# 4_shkb_lite_mini_bt_power.net
KiCad netlist of a schematic drawn in Altium Designer
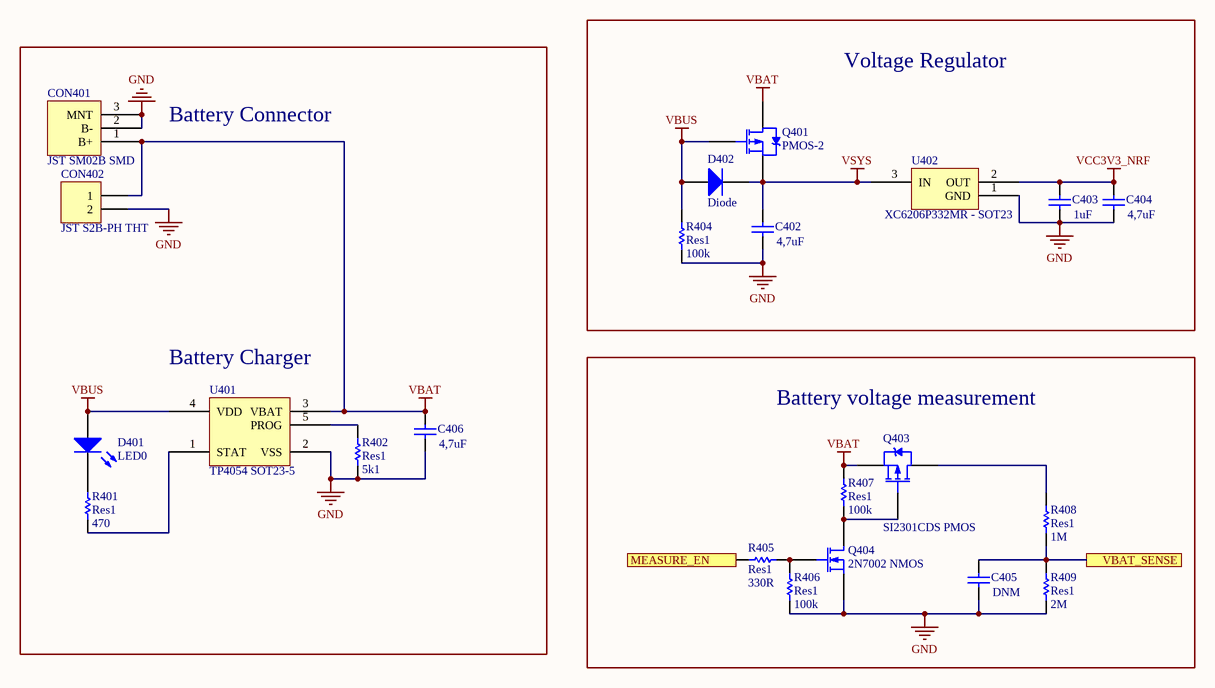
[diagram p0: 4_shkb_lite_mini_bt_power.SchDoc]

(export (version "E")
  (design (tool "Eeschema 10.0.6"))
  (components
    (comp (ref "C402")
      (value "4,7uF")
      (footprint "C0603[1608]")
      (description "Capacitor")
      (fields (field (name "LCSC PART #") "C19666") (field (name "MRF.PART") "CL10A475KO8NNNC"))
      (libsource (lib "Miscellaneous Devices") (part "Cap"))
    )
    (comp (ref "C403")
      (value "1uF")
      (footprint "C0603[1608]")
      (description "Capacitor")
      (fields (field (name "MFG") "KEMET") (field (name "LCSC PART #") "C15849"))
      (libsource (lib "Miscellaneous Devices") (part "Cap"))
    )
    (comp (ref "C404")
      (value "4,7uF")
      (footprint "C0603[1608]")
      (description "Capacitor")
      (fields (field (name "LCSC PART #") "C19666") (field (name "MRF.PART") "CL10A475KO8NNNC"))
      (libsource (lib "Miscellaneous Devices") (part "Cap"))
    )
    (comp (ref "C405")
      (value "DNM")
      (footprint "C0603[1608]")
      (description "Capacitor")
      (libsource (lib "Miscellaneous Devices") (part "Cap"))
    )
    (comp (ref "C406")
      (value "4,7uF")
      (footprint "C0603[1608]")
      (description "Capacitor")
      (fields (field (name "LCSC PART #") "C19666") (field (name "MRF.PART") "CL10A475KO8NNNC"))
      (libsource (lib "Miscellaneous Devices") (part "Cap"))
    )
    (comp (ref "CON401")
      (value "JST SM02B SMD")
      (footprint "JST SM02B-SRSS-TB")
      (fields (field (name "LCSC PART #") "C160402") (field (name "MRF.PART") "SM02B-SRSS-TB(LF)(SN)"))
      (libsource (lib "Keebs") (part "JST S2B-PH-SM4-TB"))
    )
    (comp (ref "CON402")
      (value "JST S2B-PH THT")
      (footprint "Keebs:JST S2B-PH-K(LF)(SN)")
      (description "Header, 2-Pin")
      (fields (field (name "LCSC PART #") "C265016") (field (name "MRF.PART") "S2B-PH-K(LF)(SN)"))
      (libsource (lib "Miscellaneous Connectors") (part "Header 2"))
    )
    (comp (ref "D401")
      (value "LED0")
      (footprint "LED0603[1608]")
      (description "Typical INFRARED GaAs LED")
      (fields (field (name "LCSC PART #") "C72038") (field (name "MRF.PART") "19-213/Y2C-CQ2R2L/3T(CY)"))
      (libsource (lib "Miscellaneous Devices") (part "LED0"))
    )
    (comp (ref "D402")
      (value "Diode")
      (footprint "SOD-123")
      (description "Default Diode")
      (fields (field (name "LCSC PART #") "C8598") (field (name "MRF.PART") "B5819W"))
      (libsource (lib "Miscellaneous Devices") (part "Diode"))
    )
    (comp (ref "Q401")
      (value "PMOS-2")
      (footprint "SOT-23-3")
      (description "P-Channel Power MOSFET")
      (fields (field (name "MRF.PART") "SI2301CDS-T1-GE3") (field (name "LCSC PART #") "C10487"))
      (libsource (lib "Miscellaneous Devices") (part "PMOS-2"))
    )
    (comp (ref "Q403")
      (value "SI2301CDS PMOS")
      (footprint "SOT-23-3")
      (description "P-Channel Power MOSFET")
      (fields (field (name "MRF.PART") "SI2301CDS-T1-GE3") (field (name "LCSC PART #") "C10487"))
      (libsource (lib "Miscellaneous Devices") (part "PMOS-2"))
    )
    (comp (ref "Q404")
      (value "2N7002 NMOS")
      (footprint "SOT-23-3")
      (description "N-Channel MOSFET")
      (fields (field (name "LCSC PART #") "C8545") (field (name "MRF.PART") "2N7002"))
      (libsource (lib "Miscellaneous Devices") (part "MOSFET-N"))
    )
    (comp (ref "R401")
      (value "Res1")
      (footprint "R0603[1608]")
      (description "Resistor")
      (fields
        (field (name "ALTIUM_VALUE") "470")
        (field (name "MFG") "Panasonic Electronic Components")
        (field (name "LCSC PART #") "C23179")
      )
      (libsource (lib "Miscellaneous Devices") (part "Res1"))
    )
    (comp (ref "R402")
      (value "Res1")
      (footprint "R0603[1608]")
      (description "Resistor")
      (fields
        (field (name "ALTIUM_VALUE") "5k1")
        (field (name "MFG") "Panasonic Electronic Components")
        (field (name "LCSC PART #") "C23186")
      )
      (libsource (lib "Miscellaneous Devices") (part "Res1"))
    )
    (comp (ref "R404")
      (value "Res1")
      (footprint "R0603[1608]")
      (description "Resistor")
      (fields
        (field (name "ALTIUM_VALUE") "100k")
        (field (name "MRF.PART") "0603WAF1003T5E")
        (field (name "LCSC PART #") "C25803")
      )
      (libsource (lib "Miscellaneous Devices") (part "Res1"))
    )
    (comp (ref "R405")
      (value "Res1")
      (footprint "R0603[1608]")
      (description "Resistor")
      (fields
        (field (name "ALTIUM_VALUE") "330R")
        (field (name "LCSC PART #") "C23138")
        (field (name "MRF.PART") "0603WAF3300T5E")
      )
      (libsource (lib "Miscellaneous Devices") (part "Res1"))
    )
    (comp (ref "R406")
      (value "Res1")
      (footprint "R0603[1608]")
      (description "Resistor")
      (fields
        (field (name "ALTIUM_VALUE") "100k")
        (field (name "MRF.PART") "0603WAF1003T5E")
        (field (name "LCSC PART #") "C25803")
      )
      (libsource (lib "Miscellaneous Devices") (part "Res1"))
    )
    (comp (ref "R407")
      (value "Res1")
      (footprint "R0603[1608]")
      (description "Resistor")
      (fields
        (field (name "ALTIUM_VALUE") "100k")
        (field (name "MRF.PART") "0603WAF1003T5E")
        (field (name "LCSC PART #") "C25803")
      )
      (libsource (lib "Miscellaneous Devices") (part "Res1"))
    )
    (comp (ref "R408")
      (value "Res1")
      (footprint "R0603[1608]")
      (description "Resistor")
      (fields
        (field (name "ALTIUM_VALUE") "1M")
        (field (name "MRF.PART") "0603WAF1004T5E")
        (field (name "LCSC PART #") "C22935")
      )
      (libsource (lib "Miscellaneous Devices") (part "Res1"))
    )
    (comp (ref "R409")
      (value "Res1")
      (footprint "R0603[1608]")
      (description "Resistor")
      (fields
        (field (name "ALTIUM_VALUE") "2M")
        (field (name "MRF.PART") "0603WAF2004T5E")
        (field (name "LCSC PART #") "C22976")
      )
      (libsource (lib "Miscellaneous Devices") (part "Res1"))
    )
    (comp (ref "U401")
      (value "TP4054 SOT23-5")
      (footprint "SOT-23-5")
      (fields (field (name "LCSC PART #") "C32574") (field (name "MRF.PART") "TP4054"))
      (libsource (lib "Keebs") (part "MCP73831"))
    )
    (comp (ref "U402")
      (value "XC6206P332MR - SOT23")
      (footprint "SOT-23-3")
      (fields
        (field (name "LCSC PART #") "C5446")
        (field (name "MRF.PART") "XC6206P332MR")
        (field (name "MFG") "Texas Instruments")
      )
      (libsource (lib "Keebs") (part "SOT23 LDO"))
    )
  )
  (nets
    (net (code "1") (name "/MEASURE_EN") (class "Default")
      (node (ref "R405") (pin "1") (pinfunction "1_1") (pintype "passive"))
    )
    (net (code "2") (name "/VBAT_SENSE") (class "Default")
      (node (ref "C405") (pin "2") (pinfunction "2_2") (pintype "passive"))
      (node (ref "R408") (pin "2") (pinfunction "2_2") (pintype "passive"))
      (node (ref "R409") (pin "1") (pinfunction "1_1") (pintype "passive"))
    )
    (net (code "3") (name "GND") (class "Default")
      (node (ref "C402") (pin "1") (pinfunction "1_1") (pintype "passive"))
      (node (ref "C403") (pin "1") (pinfunction "1_1") (pintype "passive"))
      (node (ref "C404") (pin "1") (pinfunction "1_1") (pintype "passive"))
      (node (ref "C405") (pin "1") (pinfunction "1_1") (pintype "passive"))
      (node (ref "C406") (pin "1") (pinfunction "1_1") (pintype "passive"))
      (node (ref "CON401") (pin "2") (pinfunction "B-_2") (pintype "passive"))
      (node (ref "CON401") (pin "3") (pinfunction "MNT_3") (pintype "passive"))
      (node (ref "CON402") (pin "2") (pinfunction "2_2") (pintype "passive"))
      (node (ref "Q404") (pin "2") (pinfunction "S_2") (pintype "passive"))
      (node (ref "R402") (pin "2") (pinfunction "2_2") (pintype "passive"))
      (node (ref "R404") (pin "2") (pinfunction "2_2") (pintype "passive"))
      (node (ref "R406") (pin "2") (pinfunction "2_2") (pintype "passive"))
      (node (ref "R409") (pin "2") (pinfunction "2_2") (pintype "passive"))
      (node (ref "U401") (pin "2") (pinfunction "VSS_2") (pintype "passive"))
      (node (ref "U402") (pin "1") (pinfunction "GND_1") (pintype "passive"))
    )
    (net (code "4") (name "Net-(D401-K)") (class "Default")
      (node (ref "D401") (pin "2") (pinfunction "K_2") (pintype "passive"))
      (node (ref "R401") (pin "2") (pinfunction "2_2") (pintype "passive"))
    )
    (net (code "5") (name "Net-(Q403-D)") (class "Default")
      (node (ref "Q403") (pin "3") (pinfunction "D_3") (pintype "passive"))
      (node (ref "R408") (pin "1") (pinfunction "1_1") (pintype "passive"))
    )
    (net (code "6") (name "Net-(Q403-G)") (class "Default")
      (node (ref "Q403") (pin "1") (pinfunction "G_1") (pintype "passive"))
      (node (ref "Q404") (pin "3") (pinfunction "D_3") (pintype "passive"))
      (node (ref "R407") (pin "2") (pinfunction "2_2") (pintype "passive"))
    )
    (net (code "7") (name "Net-(Q404-G)") (class "Default")
      (node (ref "Q404") (pin "1") (pinfunction "G_1") (pintype "passive"))
      (node (ref "R405") (pin "2") (pinfunction "2_2") (pintype "passive"))
      (node (ref "R406") (pin "1") (pinfunction "1_1") (pintype "passive"))
    )
    (net (code "8") (name "Net-(U401-PROG)") (class "Default")
      (node (ref "R402") (pin "1") (pinfunction "1_1") (pintype "passive"))
      (node (ref "U401") (pin "5") (pinfunction "PROG_5") (pintype "passive"))
    )
    (net (code "9") (name "Net-(U401-STAT)") (class "Default")
      (node (ref "R401") (pin "1") (pinfunction "1_1") (pintype "passive"))
      (node (ref "U401") (pin "1") (pinfunction "STAT_1") (pintype "passive"))
    )
    (net (code "10") (name "VBAT") (class "Default")
      (node (ref "C406") (pin "2") (pinfunction "2_2") (pintype "passive"))
      (node (ref "CON401") (pin "1") (pinfunction "B+_1") (pintype "passive"))
      (node (ref "CON402") (pin "1") (pinfunction "1_1") (pintype "passive"))
      (node (ref "Q401") (pin "3") (pinfunction "D_3") (pintype "passive"))
      (node (ref "Q403") (pin "2") (pinfunction "S_2") (pintype "passive"))
      (node (ref "R407") (pin "1") (pinfunction "1_1") (pintype "passive"))
      (node (ref "U401") (pin "3") (pinfunction "VBAT_3") (pintype "passive"))
    )
    (net (code "11") (name "VBUS") (class "Default")
      (node (ref "D401") (pin "1") (pinfunction "A_1") (pintype "passive"))
      (node (ref "D402") (pin "1") (pinfunction "A_1") (pintype "passive"))
      (node (ref "Q401") (pin "1") (pinfunction "G_1") (pintype "passive"))
      (node (ref "R404") (pin "1") (pinfunction "1_1") (pintype "passive"))
      (node (ref "U401") (pin "4") (pinfunction "VDD_4") (pintype "passive"))
    )
    (net (code "12") (name "VCC3V3_NRF") (class "Default")
      (node (ref "C403") (pin "2") (pinfunction "2_2") (pintype "passive"))
      (node (ref "C404") (pin "2") (pinfunction "2_2") (pintype "passive"))
      (node (ref "U402") (pin "2") (pinfunction "OUT_2") (pintype "passive"))
    )
    (net (code "13") (name "VSYS") (class "Default")
      (node (ref "C402") (pin "2") (pinfunction "2_2") (pintype "passive"))
      (node (ref "D402") (pin "2") (pinfunction "K_2") (pintype "passive"))
      (node (ref "Q401") (pin "2") (pinfunction "S_2") (pintype "passive"))
      (node (ref "U402") (pin "3") (pinfunction "IN_3") (pintype "passive"))
    )
  )
)
